# SCH_pie-day-pcb_2024-03-29.net
KiCad netlist of a schematic drawn in EasyEDA
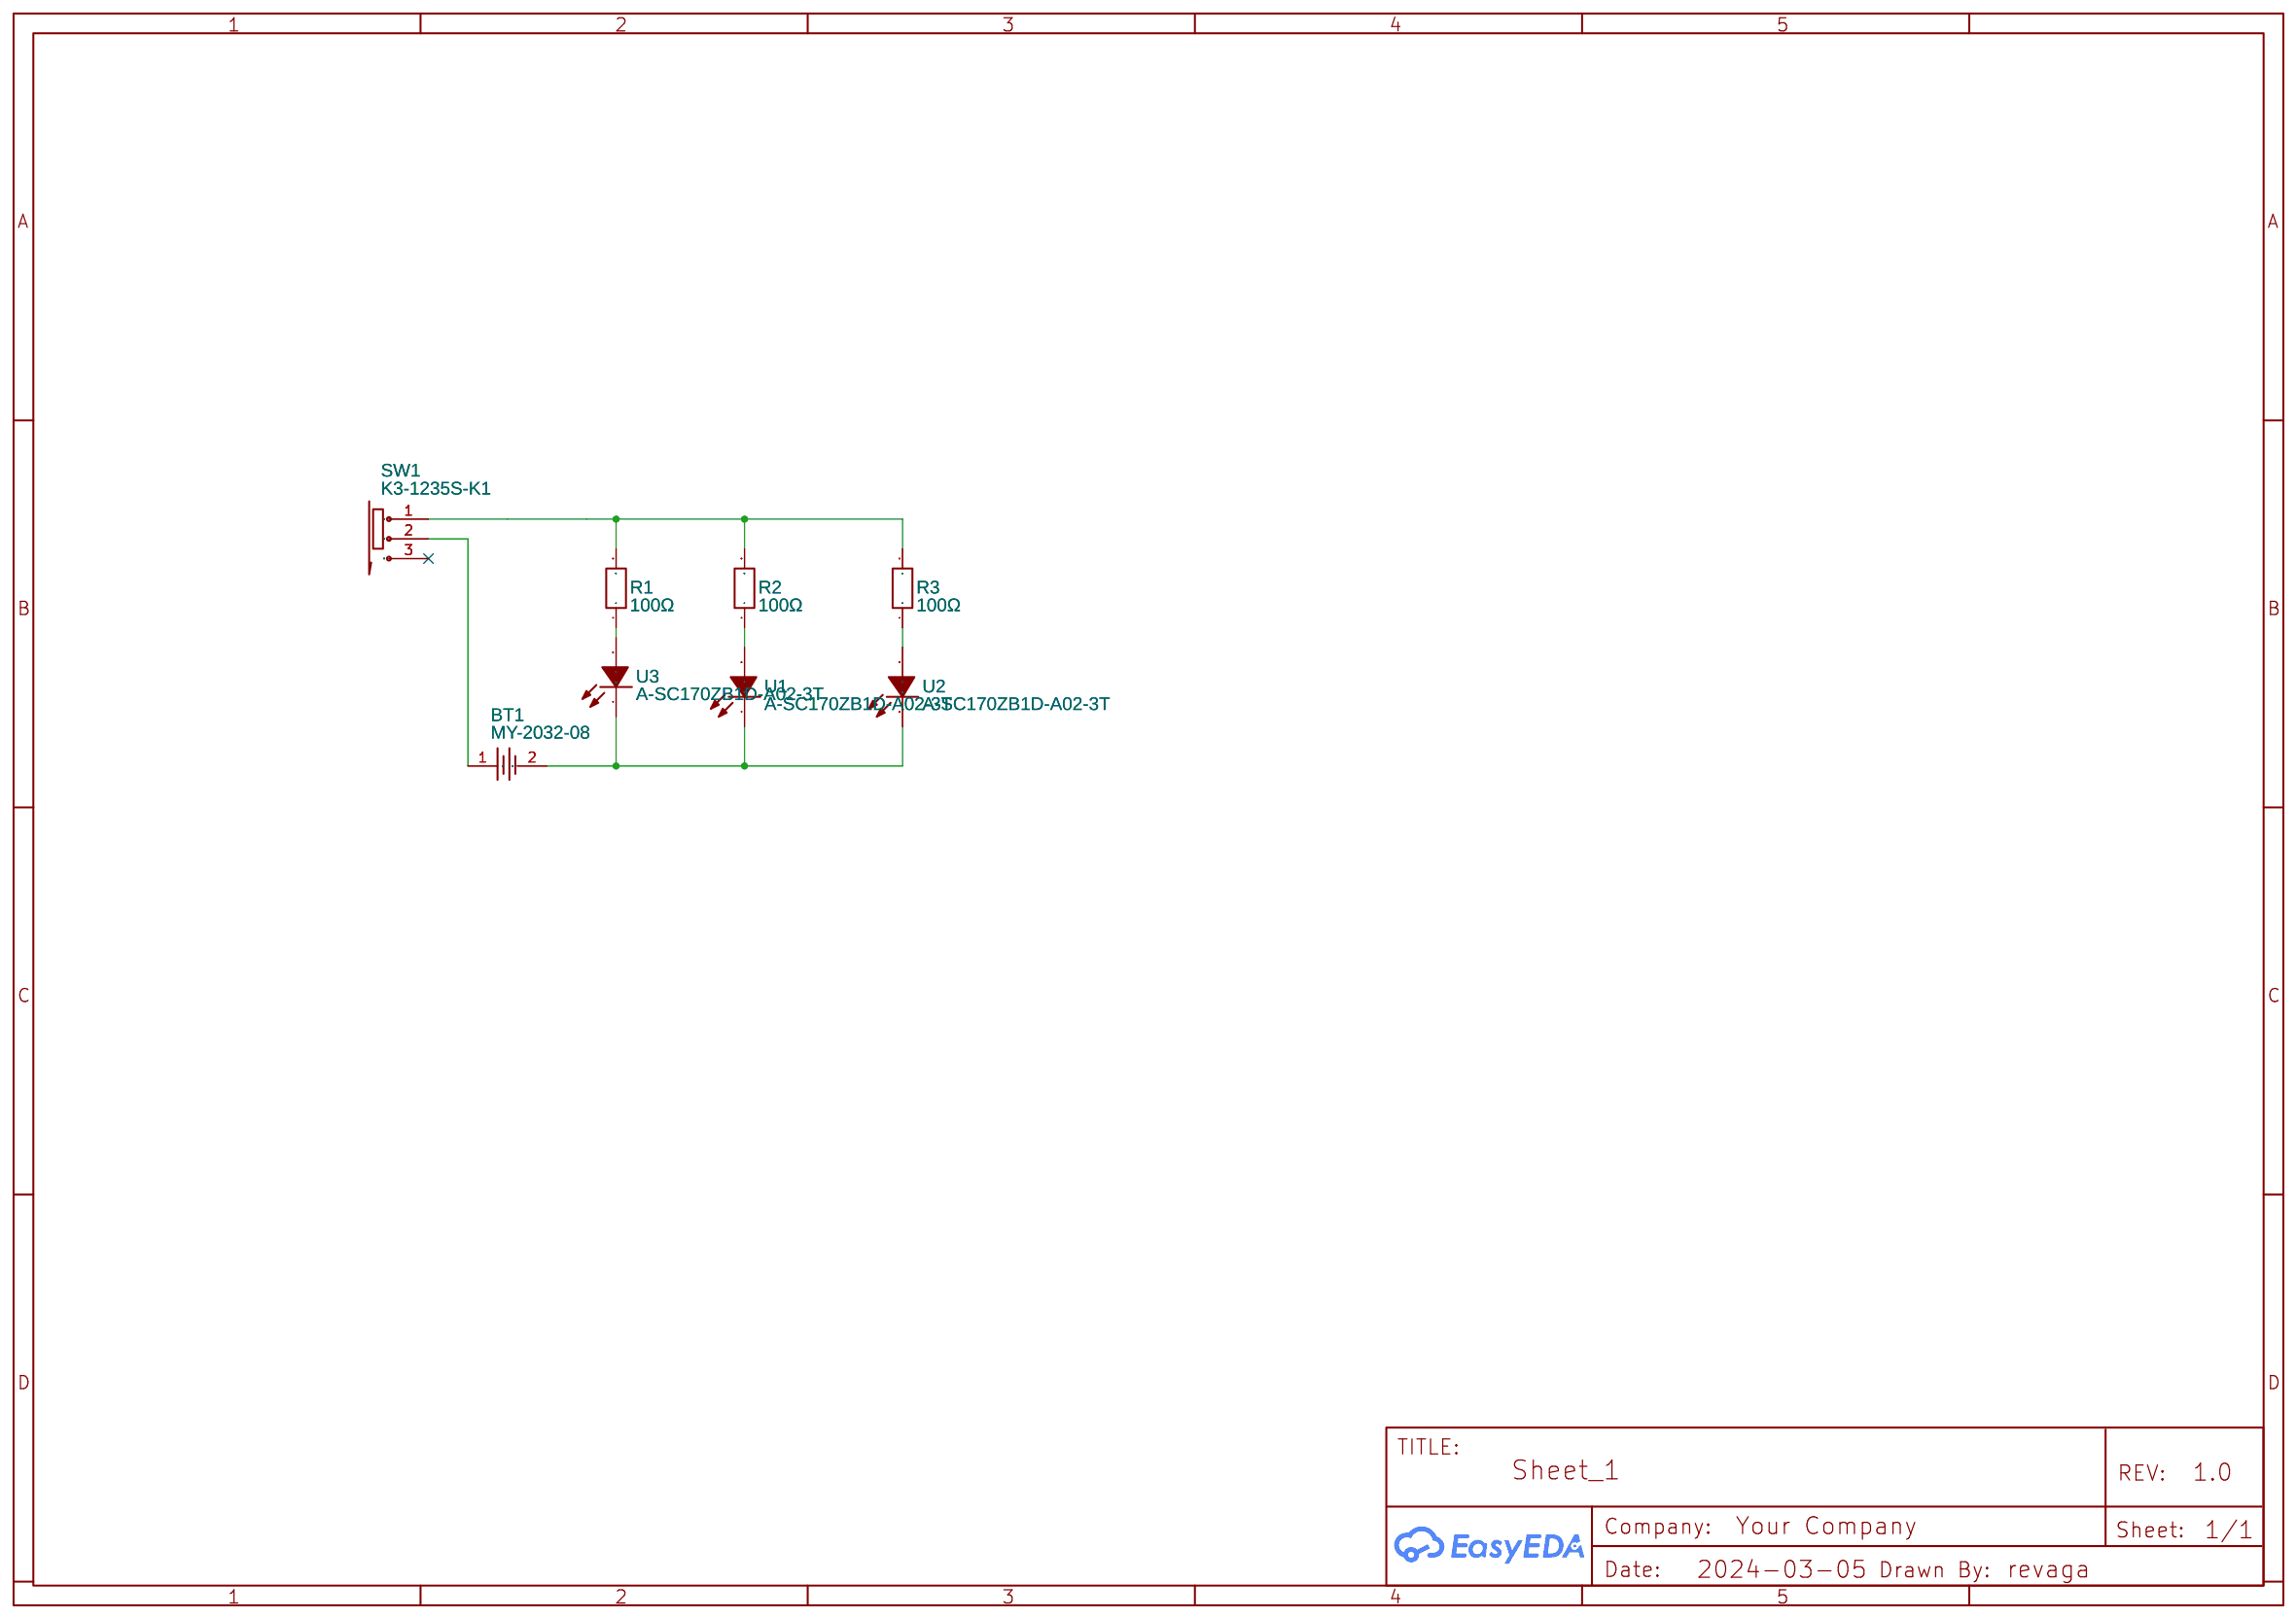
[diagram p0: schematic sheet]

(export (version "E")
  (design (tool "Eeschema 10.0.6"))
  (components
    (comp (ref "BT1")
      (value "MY-2032-08")
      (fields (field (name "Manufacturer") "MYOUNG(美阳)"))
      (libsource (lib "") (part "MY-2032-08"))
    )
    (comp (ref "R1")
      (value "100Ω")
      (fields (field (name "Manufacturer Part") "SCR0402F100R") (field (name "Manufacturer") "VO(翔胜)"))
      (libsource (lib "") (part "SCR0402F100R"))
    )
    (comp (ref "R2")
      (value "100Ω")
      (fields (field (name "Manufacturer Part") "SCR0402F100R") (field (name "Manufacturer") "VO(翔胜)"))
      (libsource (lib "") (part "SCR0402F100R"))
    )
    (comp (ref "R3")
      (value "100Ω")
      (fields (field (name "Manufacturer Part") "SCR0402F100R") (field (name "Manufacturer") "VO(翔胜)"))
      (libsource (lib "") (part "SCR0402F100R"))
    )
    (comp (ref "SW1")
      (value "K3-1235S-K1")
      (fields (field (name "Manufacturer") "韩国韩荣"))
      (libsource (lib "") (part "K3-1235S-K1"))
    )
    (comp (ref "U1")
      (value "A-SC170ZB1D-A02-3T")
      (fields (field (name "Manufacturer") "Amicc(欧密格光电)"))
      (libsource (lib "") (part "A-SC170ZB1D-A02-3T"))
    )
    (comp (ref "U2")
      (value "A-SC170ZB1D-A02-3T")
      (fields (field (name "Manufacturer") "Amicc(欧密格光电)"))
      (libsource (lib "") (part "A-SC170ZB1D-A02-3T"))
    )
    (comp (ref "U3")
      (value "A-SC170ZB1D-A02-3T")
      (fields (field (name "Manufacturer") "Amicc(欧密格光电)"))
      (libsource (lib "") (part "A-SC170ZB1D-A02-3T"))
    )
  )
  (nets
    (net (code "1") (name "Net-(BT1-Pad1)") (class "Default")
      (node (ref "BT1") (pin "1") (pinfunction "1_1") (pintype "input"))
      (node (ref "SW1") (pin "2") (pinfunction "2_2") (pintype "unspecified"))
    )
    (net (code "2") (name "Net-(R1-Pad2)") (class "Default")
      (node (ref "R1") (pin "2") (pinfunction "2_2") (pintype "unspecified"))
      (node (ref "R2") (pin "2") (pinfunction "2_2") (pintype "unspecified"))
      (node (ref "R3") (pin "2") (pinfunction "2_2") (pintype "unspecified"))
      (node (ref "SW1") (pin "1") (pinfunction "1_1") (pintype "unspecified"))
    )
    (net (code "3") (name "Net-(U1-A)") (class "Default")
      (node (ref "R2") (pin "1") (pinfunction "1_1") (pintype "unspecified"))
      (node (ref "U1") (pin "2") (pinfunction "A_2") (pintype "unspecified"))
    )
    (net (code "4") (name "Net-(U1-C)") (class "Default")
      (node (ref "BT1") (pin "2") (pinfunction "2_2") (pintype "input"))
      (node (ref "U1") (pin "1") (pinfunction "C_1") (pintype "unspecified"))
      (node (ref "U2") (pin "1") (pinfunction "C_1") (pintype "unspecified"))
      (node (ref "U3") (pin "1") (pinfunction "C_1") (pintype "unspecified"))
    )
    (net (code "5") (name "Net-(U2-A)") (class "Default")
      (node (ref "R3") (pin "1") (pinfunction "1_1") (pintype "unspecified"))
      (node (ref "U2") (pin "2") (pinfunction "A_2") (pintype "unspecified"))
    )
    (net (code "6") (name "Net-(U3-A)") (class "Default")
      (node (ref "R1") (pin "1") (pinfunction "1_1") (pintype "unspecified"))
      (node (ref "U3") (pin "2") (pinfunction "A_2") (pintype "unspecified"))
    )
    (net (code "7") (name "unconnected-(SW1-Pad3)") (class "Default")
      (node (ref "SW1") (pin "3") (pinfunction "3_3") (pintype "unspecified+no_connect"))
    )
  )
)
